# 4_SD_Card.net
KiCad netlist of a schematic drawn in Altium Designer
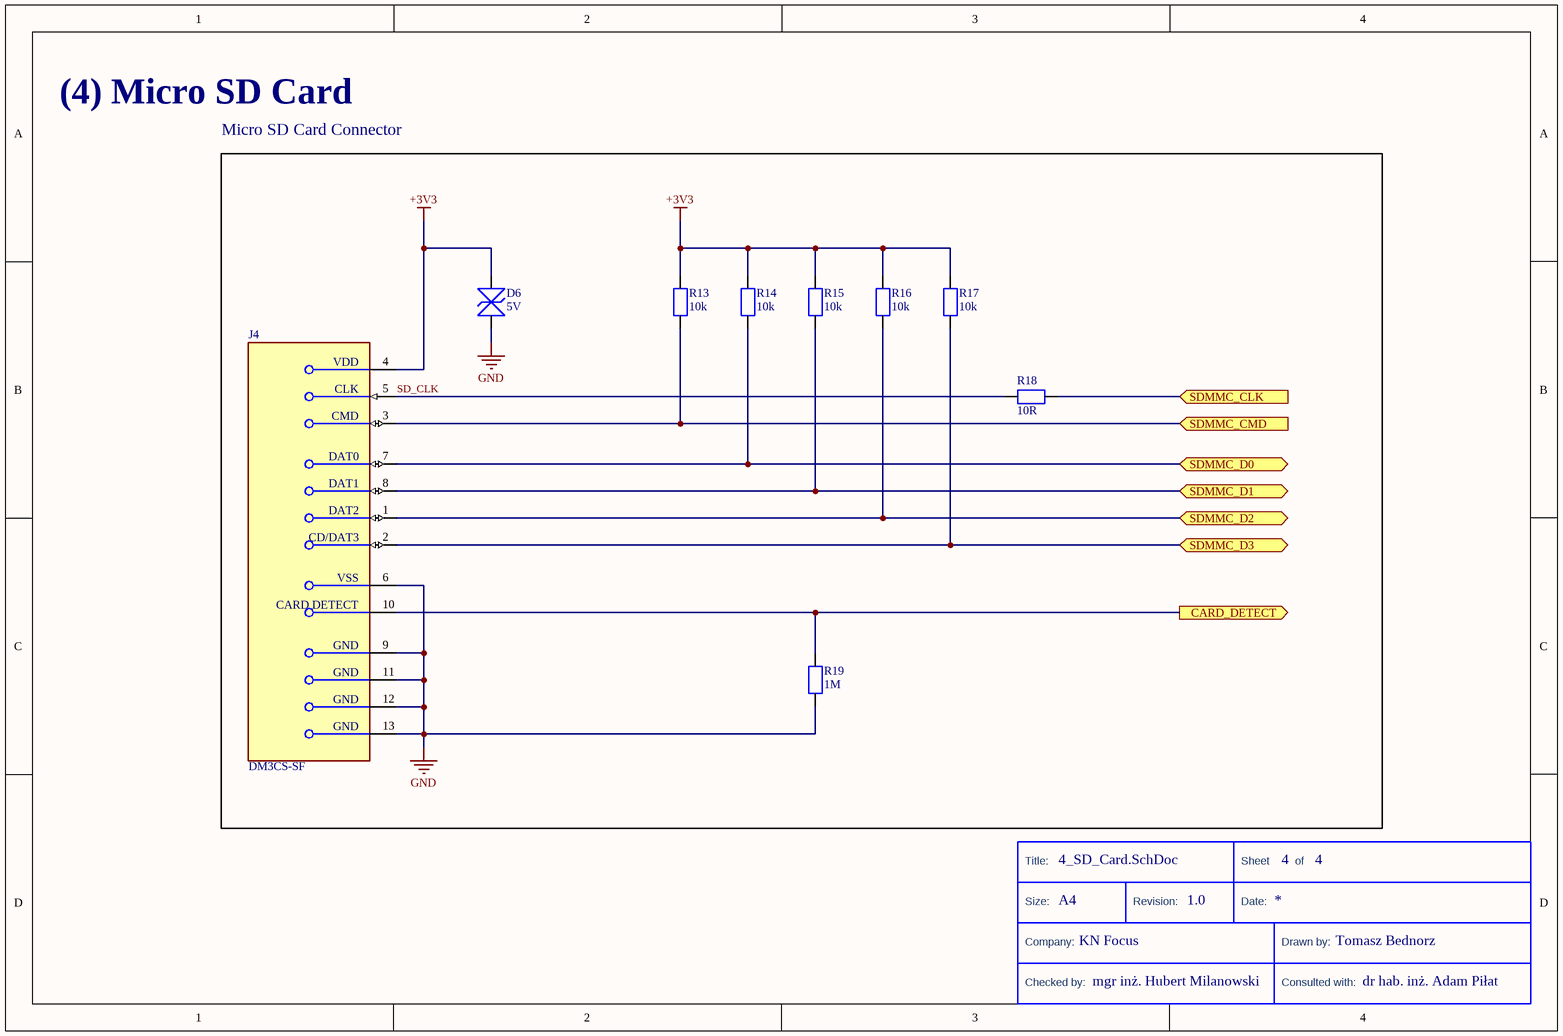
[diagram p0: 4_SD_Card.SchDoc]

(export (version "E")
  (design (tool "Eeschema 10.0.6"))
  (components
    (comp (ref "D6")
      (value "5V")
      (footprint "TVS_Littlefuse")
      (description "TVS Diode TVS_SMAJ5.0CA  5V Bidirectional")
      (libsource (lib "SymbolLib") (part "TVS_5V"))
    )
    (comp (ref "J4")
      (value "DM3CS-SF")
      (footprint "FP-DM3CS-SF-MFG")
      (description "CONN MICRO SD CARD HINGED TYPE")
      (libsource (lib "Altium Content Vault") (part "bac915de5305cfdd1ca301aae530106"))
    )
    (comp (ref "R13")
      (value "10k")
      (footprint "RES_1206")
      (description "Generic 1206/3216 resistor")
      (libsource (lib "SymbolLib") (part "RES_1206"))
    )
    (comp (ref "R14")
      (value "10k")
      (footprint "RES_1206")
      (description "Generic 1206/3216 resistor")
      (libsource (lib "SymbolLib") (part "RES_1206"))
    )
    (comp (ref "R15")
      (value "10k")
      (footprint "RES_1206")
      (description "Generic 1206/3216 resistor")
      (libsource (lib "SymbolLib") (part "RES_1206"))
    )
    (comp (ref "R16")
      (value "10k")
      (footprint "RES_1206")
      (description "Generic 1206/3216 resistor")
      (libsource (lib "SymbolLib") (part "RES_1206"))
    )
    (comp (ref "R17")
      (value "10k")
      (footprint "RES_1206")
      (description "Generic 1206/3216 resistor")
      (libsource (lib "SymbolLib") (part "RES_1206"))
    )
    (comp (ref "R18")
      (value "10R")
      (footprint "RES_1206")
      (description "Generic 1206/3216 resistor")
      (libsource (lib "SymbolLib") (part "RES_1206"))
    )
    (comp (ref "R19")
      (value "1M")
      (footprint "RES_1206")
      (description "Generic 1206/3216 resistor")
      (libsource (lib "SymbolLib") (part "RES_1206"))
    )
  )
  (nets
    (net (code "1") (name "+3V3") (class "Default")
      (node (ref "D6") (pin "1") (pinfunction "1_1") (pintype "passive"))
      (node (ref "J4") (pin "4") (pinfunction "VDD_4") (pintype "power_in"))
      (node (ref "R13") (pin "2") (pinfunction "2_2") (pintype "passive"))
      (node (ref "R14") (pin "2") (pinfunction "2_2") (pintype "passive"))
      (node (ref "R15") (pin "2") (pinfunction "2_2") (pintype "passive"))
      (node (ref "R16") (pin "2") (pinfunction "2_2") (pintype "passive"))
      (node (ref "R17") (pin "2") (pinfunction "2_2") (pintype "passive"))
    )
    (net (code "2") (name "/CARD_DETECT") (class "Default")
      (node (ref "J4") (pin "10") (pinfunction "CARD_DETECT_10") (pintype "passive"))
      (node (ref "R19") (pin "1") (pinfunction "1_1") (pintype "passive"))
    )
    (net (code "3") (name "/SDMMC_CLK") (class "Default")
      (node (ref "R18") (pin "1") (pinfunction "1_1") (pintype "passive"))
    )
    (net (code "4") (name "/SDMMC_CMD") (class "Default")
      (node (ref "J4") (pin "3") (pinfunction "CMD_3") (pintype "bidirectional"))
      (node (ref "R13") (pin "1") (pinfunction "1_1") (pintype "passive"))
    )
    (net (code "5") (name "/SDMMC_D0") (class "Default")
      (node (ref "J4") (pin "7") (pinfunction "DAT0_7") (pintype "bidirectional"))
      (node (ref "R14") (pin "1") (pinfunction "1_1") (pintype "passive"))
    )
    (net (code "6") (name "/SDMMC_D1") (class "Default")
      (node (ref "J4") (pin "8") (pinfunction "DAT1_8") (pintype "bidirectional"))
      (node (ref "R15") (pin "1") (pinfunction "1_1") (pintype "passive"))
    )
    (net (code "7") (name "/SDMMC_D2") (class "Default")
      (node (ref "J4") (pin "1") (pinfunction "DAT2_1") (pintype "bidirectional"))
      (node (ref "R16") (pin "1") (pinfunction "1_1") (pintype "passive"))
    )
    (net (code "8") (name "/SDMMC_D3") (class "Default")
      (node (ref "J4") (pin "2") (pinfunction "CD/DAT3_2") (pintype "bidirectional"))
      (node (ref "R17") (pin "1") (pinfunction "1_1") (pintype "passive"))
    )
    (net (code "9") (name "/SD_CLK") (class "Default")
      (node (ref "J4") (pin "5") (pinfunction "CLK_5") (pintype "input"))
      (node (ref "R18") (pin "2") (pinfunction "2_2") (pintype "passive"))
    )
    (net (code "10") (name "GND") (class "Default")
      (node (ref "D6") (pin "2") (pinfunction "2_2") (pintype "passive"))
      (node (ref "J4") (pin "11") (pinfunction "GND_11") (pintype "power_in"))
      (node (ref "J4") (pin "12") (pinfunction "GND_12") (pintype "power_in"))
      (node (ref "J4") (pin "13") (pinfunction "GND_13") (pintype "power_in"))
      (node (ref "J4") (pin "6") (pinfunction "VSS_6") (pintype "power_in"))
      (node (ref "J4") (pin "9") (pinfunction "GND_9") (pintype "power_in"))
      (node (ref "R19") (pin "2") (pinfunction "2_2") (pintype "passive"))
    )
  )
)
